# 3M_Repair.net
KiCad netlist of a schematic drawn in EAGLE
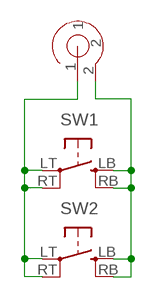
[diagram p0: schematic, sheet 1]

(export (version "E")
  (design (tool "Eeschema 10.0.6"))
  (components
    (comp (ref "P1")
      (value "3M_PR")
      (footprint "eagle-import:3M_PR")
      (libsource (lib "eagle-import") (part "3M_PR"))
    )
    (comp (ref "SW1")
      (value "PUSH_BUTTON6X6")
      (footprint "eagle-import:6X6")
      (libsource (lib "eagle-import") (part "PUSH_BUTTON6X6"))
    )
    (comp (ref "SW2")
      (value "PUSH_BUTTON12X12")
      (footprint "eagle-import:12X12")
      (libsource (lib "eagle-import") (part "PUSH_BUTTON12X12"))
    )
  )
  (nets
    (net (code "1") (name "Net-(P1-Pad1)") (class "Default")
      (node (ref "P1") (pin "1") (pinfunction "1_1") (pintype "bidirectional"))
      (node (ref "SW1") (pin "LT") (pinfunction "LT_LT") (pintype "passive"))
      (node (ref "SW1") (pin "RT") (pinfunction "RT_RT") (pintype "passive"))
      (node (ref "SW2") (pin "LT") (pinfunction "LT_LT") (pintype "passive"))
      (node (ref "SW2") (pin "RT") (pinfunction "RT_RT") (pintype "passive"))
    )
    (net (code "2") (name "Net-(P1-Pad2)") (class "Default")
      (node (ref "P1") (pin "2") (pinfunction "2_2") (pintype "bidirectional"))
      (node (ref "SW1") (pin "LB") (pinfunction "LB_LB") (pintype "passive"))
      (node (ref "SW1") (pin "RB") (pinfunction "RB_RB") (pintype "passive"))
      (node (ref "SW2") (pin "LB") (pinfunction "LB_LB") (pintype "passive"))
      (node (ref "SW2") (pin "RB") (pinfunction "RB_RB") (pintype "passive"))
    )
  )
)
